# board_with_sense.net
KiCad netlist of a schematic drawn in EAGLE
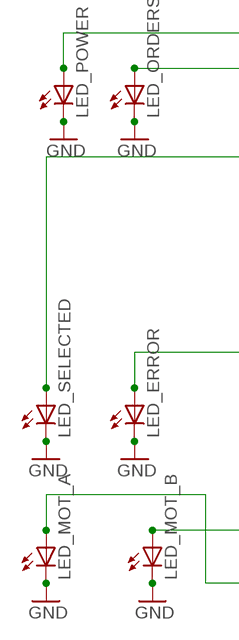
[diagram p0: schematic, sheet 1, part 1 of 2]
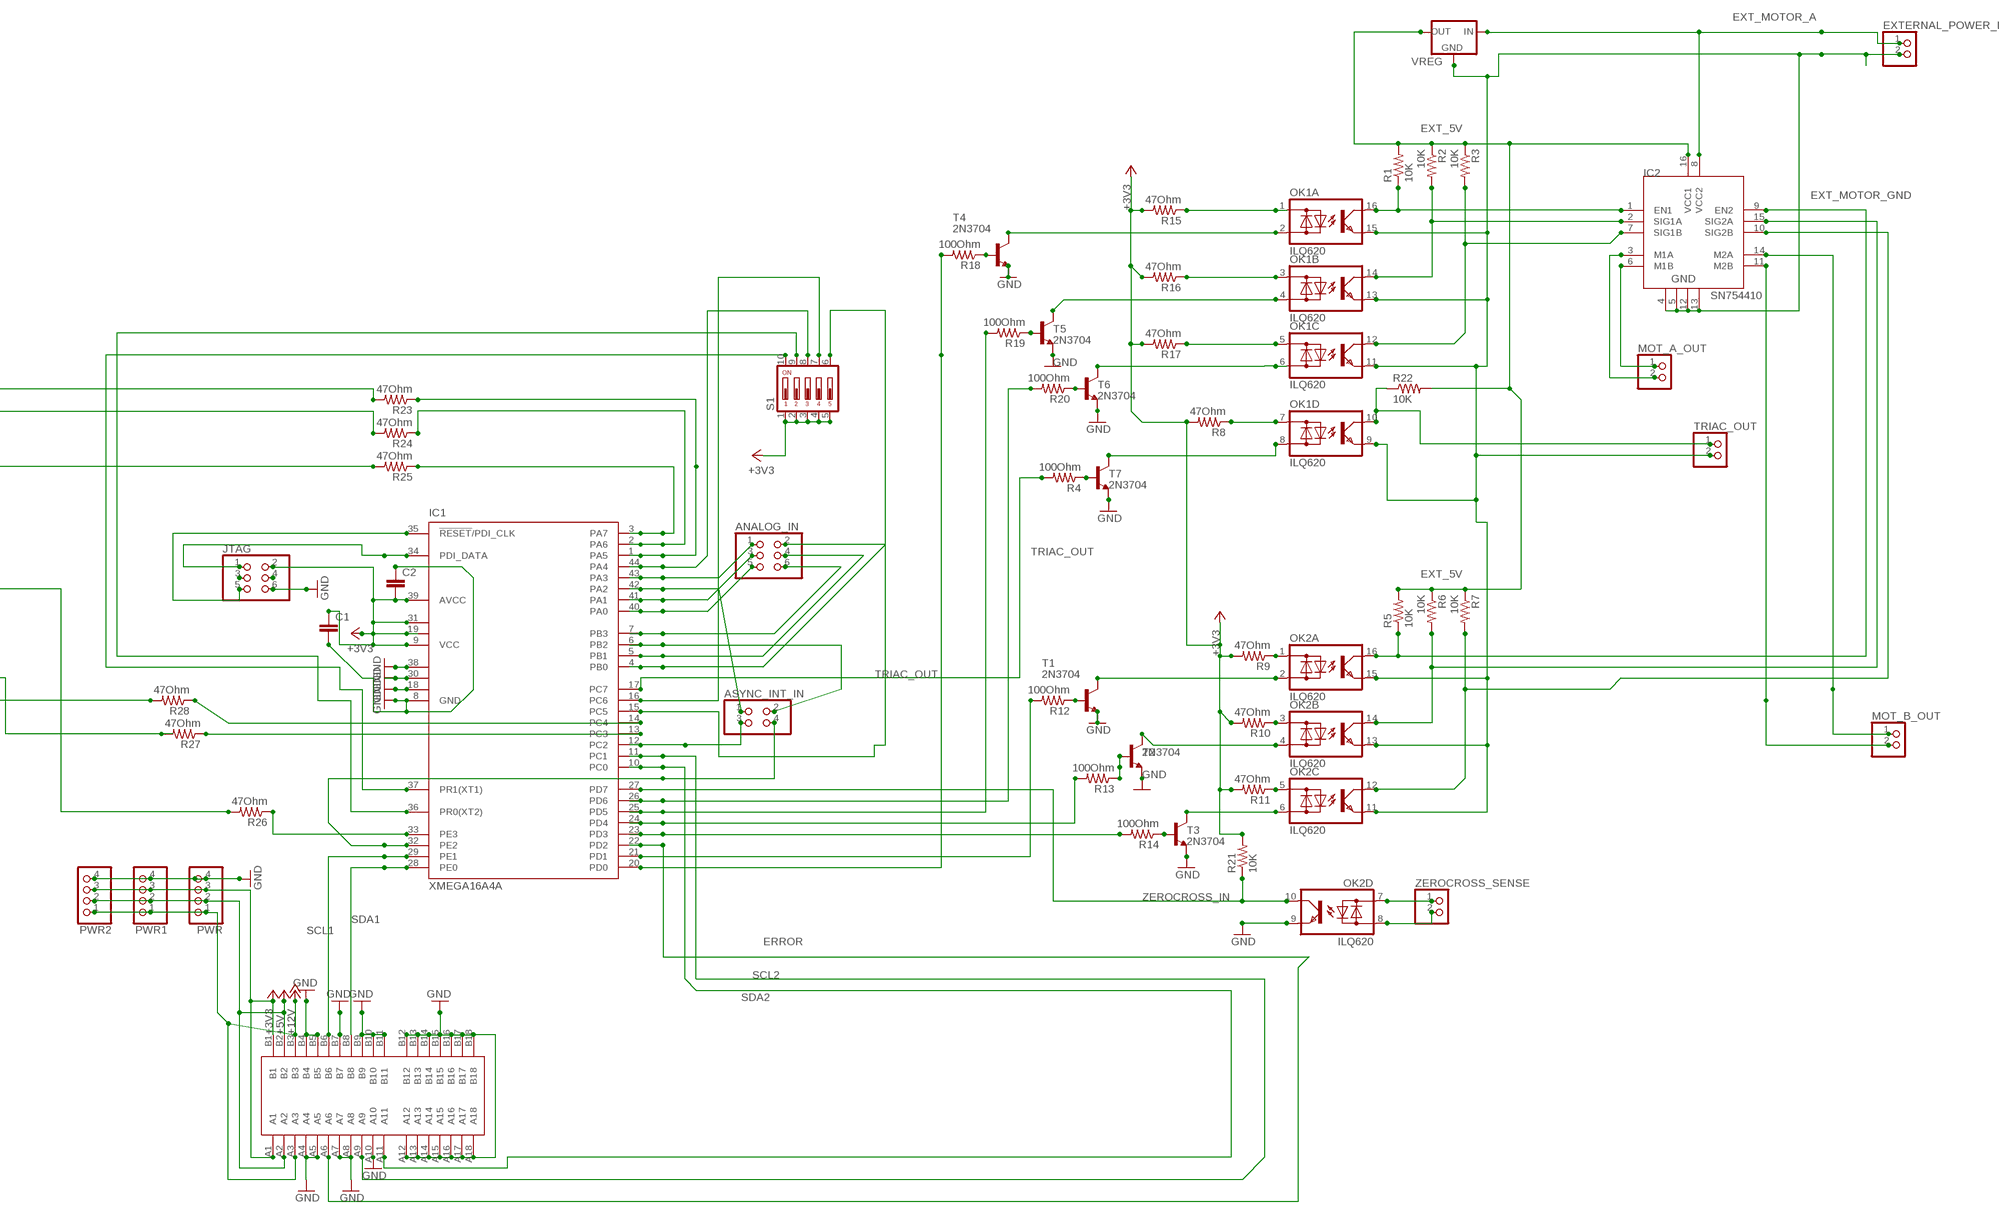
[diagram p1: schematic, sheet 1, part 2 of 2]

(export (version "E")
  (design (tool "Eeschema 10.0.6"))
  (components
    (comp (ref "ANALOG_IN")
      (value "PINHD-2X3")
      (footprint "eagle-import:2X03")
      (libsource (lib "eagle-import") (part "PINHD-2X3"))
    )
    (comp (ref "ASYNC_INT_IN")
      (value "PINHD-2X2")
      (footprint "eagle-import:2X02")
      (libsource (lib "eagle-import") (part "PINHD-2X2"))
    )
    (comp (ref "C1")
      (value "C2.5/4")
      (footprint "eagle-import:C2.5-4")
      (libsource (lib "eagle-import") (part "C2.5/4"))
    )
    (comp (ref "C2")
      (value "C2.5/4")
      (footprint "eagle-import:C2.5-4")
      (libsource (lib "eagle-import") (part "C2.5/4"))
    )
    (comp (ref "EXTERNAL_POWER_IN")
      (value "PINHD-1X2")
      (footprint "eagle-import:1X02")
      (libsource (lib "eagle-import") (part "PINHD-1X2"))
    )
    (comp (ref "IC1")
      (value "XMEGA16A4A")
      (footprint "eagle-import:TQFP44")
      (libsource (lib "eagle-import") (part "XMEGA16A4A"))
    )
    (comp (ref "IC2")
      (value "SN754410")
      (footprint "eagle-import:DIP16")
      (libsource (lib "eagle-import") (part "SN754410"))
    )
    (comp (ref "JTAG")
      (value "PINHD-2X3")
      (footprint "eagle-import:2X03")
      (libsource (lib "eagle-import") (part "PINHD-2X3"))
    )
    (comp (ref "LED_ERROR")
      (value "LED5MM")
      (footprint "eagle-import:LED5MM")
      (libsource (lib "eagle-import") (part "LED5MM"))
    )
    (comp (ref "LED_MOT_A")
      (value "LED5MM")
      (footprint "eagle-import:LED5MM")
      (libsource (lib "eagle-import") (part "LED5MM"))
    )
    (comp (ref "LED_MOT_B")
      (value "LED5MM")
      (footprint "eagle-import:LED5MM")
      (libsource (lib "eagle-import") (part "LED5MM"))
    )
    (comp (ref "LED_ORDERS")
      (value "LED5MM")
      (footprint "eagle-import:LED5MM")
      (libsource (lib "eagle-import") (part "LED5MM"))
    )
    (comp (ref "LED_POWER")
      (value "LED5MM")
      (footprint "eagle-import:LED5MM")
      (libsource (lib "eagle-import") (part "LED5MM"))
    )
    (comp (ref "LED_SELECTED")
      (value "LED5MM")
      (footprint "eagle-import:LED5MM")
      (libsource (lib "eagle-import") (part "LED5MM"))
    )
    (comp (ref "MOT_A_OUT")
      (value "PINHD-1X2")
      (footprint "eagle-import:1X02")
      (libsource (lib "eagle-import") (part "PINHD-1X2"))
    )
    (comp (ref "MOT_B_OUT")
      (value "PINHD-1X2")
      (footprint "eagle-import:1X02")
      (libsource (lib "eagle-import") (part "PINHD-1X2"))
    )
    (comp (ref "OK1")
      (value "ILQ620")
      (footprint "eagle-import:DIL16")
      (libsource (lib "eagle-import") (part "ILQ620"))
    )
    (comp (ref "OK2")
      (value "ILQ620")
      (footprint "eagle-import:DIL16")
      (libsource (lib "eagle-import") (part "ILQ620"))
    )
    (comp (ref "PWR")
      (value "PINHD-1X4")
      (footprint "eagle-import:1X04")
      (libsource (lib "eagle-import") (part "PINHD-1X4"))
    )
    (comp (ref "PWR1")
      (value "PINHD-1X4")
      (footprint "eagle-import:1X04")
      (libsource (lib "eagle-import") (part "PINHD-1X4"))
    )
    (comp (ref "PWR2")
      (value "PINHD-1X4")
      (footprint "eagle-import:1X04")
      (libsource (lib "eagle-import") (part "PINHD-1X4"))
    )
    (comp (ref "R1")
      (value "10K")
      (footprint "eagle-import:R0805")
      (libsource (lib "eagle-import") (part "R-US_R0805"))
    )
    (comp (ref "R2")
      (value "10K")
      (footprint "eagle-import:R0805")
      (libsource (lib "eagle-import") (part "R-US_R0805"))
    )
    (comp (ref "R3")
      (value "10K")
      (footprint "eagle-import:R0805")
      (libsource (lib "eagle-import") (part "R-US_R0805"))
    )
    (comp (ref "R4")
      (value "100Ohm")
      (footprint "eagle-import:0207_10")
      (libsource (lib "eagle-import") (part "R-US_0207/10"))
    )
    (comp (ref "R5")
      (value "10K")
      (footprint "eagle-import:R0805")
      (libsource (lib "eagle-import") (part "R-US_R0805"))
    )
    (comp (ref "R6")
      (value "10K")
      (footprint "eagle-import:R0805")
      (libsource (lib "eagle-import") (part "R-US_R0805"))
    )
    (comp (ref "R7")
      (value "10K")
      (footprint "eagle-import:R0805")
      (libsource (lib "eagle-import") (part "R-US_R0805"))
    )
    (comp (ref "R8")
      (value "47Ohm")
      (footprint "eagle-import:0207_10")
      (libsource (lib "eagle-import") (part "R-US_0207/10"))
    )
    (comp (ref "R9")
      (value "47Ohm")
      (footprint "eagle-import:0207_10")
      (libsource (lib "eagle-import") (part "R-US_0207/10"))
    )
    (comp (ref "R10")
      (value "47Ohm")
      (footprint "eagle-import:0207_10")
      (libsource (lib "eagle-import") (part "R-US_0207/10"))
    )
    (comp (ref "R11")
      (value "47Ohm")
      (footprint "eagle-import:0207_10")
      (libsource (lib "eagle-import") (part "R-US_0207/10"))
    )
    (comp (ref "R12")
      (value "100Ohm")
      (footprint "eagle-import:0207_10")
      (libsource (lib "eagle-import") (part "R-US_0207/10"))
    )
    (comp (ref "R13")
      (value "100Ohm")
      (footprint "eagle-import:R0805")
      (libsource (lib "eagle-import") (part "R-US_R0805"))
    )
    (comp (ref "R14")
      (value "100Ohm")
      (footprint "eagle-import:R0805")
      (libsource (lib "eagle-import") (part "R-US_R0805"))
    )
    (comp (ref "R15")
      (value "47Ohm")
      (footprint "eagle-import:0207_10")
      (libsource (lib "eagle-import") (part "R-US_0207/10"))
    )
    (comp (ref "R16")
      (value "47Ohm")
      (footprint "eagle-import:0207_10")
      (libsource (lib "eagle-import") (part "R-US_0207/10"))
    )
    (comp (ref "R17")
      (value "47Ohm")
      (footprint "eagle-import:0207_10")
      (libsource (lib "eagle-import") (part "R-US_0207/10"))
    )
    (comp (ref "R18")
      (value "100Ohm")
      (footprint "eagle-import:R0805")
      (libsource (lib "eagle-import") (part "R-US_R0805"))
    )
    (comp (ref "R19")
      (value "100Ohm")
      (footprint "eagle-import:R0805")
      (libsource (lib "eagle-import") (part "R-US_R0805"))
    )
    (comp (ref "R20")
      (value "100Ohm")
      (footprint "eagle-import:R0805")
      (libsource (lib "eagle-import") (part "R-US_R0805"))
    )
    (comp (ref "R21")
      (value "10K")
      (footprint "eagle-import:0207_10")
      (libsource (lib "eagle-import") (part "R-US_0207/10"))
    )
    (comp (ref "R22")
      (value "10K")
      (footprint "eagle-import:R0805")
      (libsource (lib "eagle-import") (part "R-US_R0805"))
    )
    (comp (ref "R23")
      (value "47Ohm")
      (footprint "eagle-import:0204_7")
      (libsource (lib "eagle-import") (part "R-US_0204/7"))
    )
    (comp (ref "R24")
      (value "47Ohm")
      (footprint "eagle-import:0204_7")
      (libsource (lib "eagle-import") (part "R-US_0204/7"))
    )
    (comp (ref "R25")
      (value "47Ohm")
      (footprint "eagle-import:0204_7")
      (libsource (lib "eagle-import") (part "R-US_0204/7"))
    )
    (comp (ref "R26")
      (value "47Ohm")
      (footprint "eagle-import:0204_7")
      (libsource (lib "eagle-import") (part "R-US_0204/7"))
    )
    (comp (ref "R27")
      (value "47Ohm")
      (footprint "eagle-import:0204_7")
      (libsource (lib "eagle-import") (part "R-US_0204/7"))
    )
    (comp (ref "R28")
      (value "47Ohm")
      (footprint "eagle-import:0204_7")
      (libsource (lib "eagle-import") (part "R-US_0204/7"))
    )
    (comp (ref "S1")
      (value "DA05")
      (footprint "eagle-import:DA-05")
      (libsource (lib "eagle-import") (part "DA05"))
    )
    (comp (ref "T1")
      (value "2N3704")
      (footprint "eagle-import:TO92")
      (libsource (lib "eagle-import") (part "2N3704"))
    )
    (comp (ref "T2")
      (value "2N3704")
      (footprint "eagle-import:TO92")
      (libsource (lib "eagle-import") (part "2N3704"))
    )
    (comp (ref "T3")
      (value "2N3704")
      (footprint "eagle-import:TO92")
      (libsource (lib "eagle-import") (part "2N3704"))
    )
    (comp (ref "T4")
      (value "2N3704")
      (footprint "eagle-import:TO92")
      (libsource (lib "eagle-import") (part "2N3704"))
    )
    (comp (ref "T5")
      (value "2N3704")
      (footprint "eagle-import:TO92")
      (libsource (lib "eagle-import") (part "2N3704"))
    )
    (comp (ref "T6")
      (value "2N3704")
      (footprint "eagle-import:TO92")
      (libsource (lib "eagle-import") (part "2N3704"))
    )
    (comp (ref "T7")
      (value "2N3704")
      (footprint "eagle-import:TO92")
      (libsource (lib "eagle-import") (part "2N3704"))
    )
    (comp (ref "TRIAC_OUT")
      (value "PINHD-1X2")
      (footprint "eagle-import:1X02")
      (libsource (lib "eagle-import") (part "PINHD-1X2"))
    )
    (comp (ref "VREG")
      (value "78MXXL")
      (footprint "eagle-import:78MXXL")
      (libsource (lib "eagle-import") (part "78MXXL"))
    )
    (comp (ref "X1")
      (value "PCI-E1X_EDGE")
      (footprint "eagle-import:PCI-E_X1_EDGE")
      (libsource (lib "eagle-import") (part "PCI-E1X_EDGE"))
    )
    (comp (ref "ZEROCROSS_SENSE")
      (value "PINHD-1X2")
      (footprint "eagle-import:1X02")
      (libsource (lib "eagle-import") (part "PINHD-1X2"))
    )
  )
  (nets
    (net (code "1") (name "+3V3") (class "Default")
      (node (ref "C1") (pin "1") (pinfunction "1_1") (pintype "passive"))
      (node (ref "C2") (pin "2") (pinfunction "2_2") (pintype "passive"))
      (node (ref "IC1") (pin "19") (pinfunction "VCC1_19") (pintype "power_in"))
      (node (ref "IC1") (pin "31") (pinfunction "VCC2_31") (pintype "power_in"))
      (node (ref "IC1") (pin "39") (pinfunction "AVCC_39") (pintype "power_in"))
      (node (ref "IC1") (pin "9") (pinfunction "VCC_9") (pintype "power_in"))
      (node (ref "JTAG") (pin "2") (pinfunction "2_2") (pintype "passive"))
      (node (ref "PWR") (pin "3") (pinfunction "3_3") (pintype "passive"))
      (node (ref "PWR1") (pin "3") (pinfunction "3_3") (pintype "passive"))
      (node (ref "PWR2") (pin "3") (pinfunction "3_3") (pintype "passive"))
      (node (ref "R10") (pin "2") (pinfunction "2_2") (pintype "passive"))
      (node (ref "R11") (pin "2") (pinfunction "2_2") (pintype "passive"))
      (node (ref "R15") (pin "2") (pinfunction "2_2") (pintype "passive"))
      (node (ref "R16") (pin "2") (pinfunction "2_2") (pintype "passive"))
      (node (ref "R17") (pin "2") (pinfunction "2_2") (pintype "passive"))
      (node (ref "R21") (pin "2") (pinfunction "2_2") (pintype "passive"))
      (node (ref "R8") (pin "2") (pinfunction "2_2") (pintype "passive"))
      (node (ref "R9") (pin "2") (pinfunction "2_2") (pintype "passive"))
      (node (ref "S1") (pin "1") (pinfunction "1_1") (pintype "passive"))
      (node (ref "S1") (pin "2") (pinfunction "2_2") (pintype "passive"))
      (node (ref "S1") (pin "3") (pinfunction "3_3") (pintype "passive"))
      (node (ref "S1") (pin "4") (pinfunction "4_4") (pintype "passive"))
      (node (ref "S1") (pin "5") (pinfunction "5_5") (pintype "passive"))
      (node (ref "X1") (pin "A1") (pinfunction "A1_A1") (pintype "bidirectional"))
      (node (ref "X1") (pin "B1") (pinfunction "B1_B1") (pintype "bidirectional"))
    )
    (net (code "2") (name "+5V") (class "Default")
      (node (ref "PWR") (pin "2") (pinfunction "2_2") (pintype "passive"))
      (node (ref "PWR1") (pin "2") (pinfunction "2_2") (pintype "passive"))
      (node (ref "PWR2") (pin "2") (pinfunction "2_2") (pintype "passive"))
      (node (ref "X1") (pin "A2") (pinfunction "A2_A2") (pintype "bidirectional"))
      (node (ref "X1") (pin "B2") (pinfunction "B2_B2") (pintype "bidirectional"))
    )
    (net (code "3") (name "+12V") (class "Default")
      (node (ref "PWR") (pin "1") (pinfunction "1_1") (pintype "passive"))
      (node (ref "PWR1") (pin "1") (pinfunction "1_1") (pintype "passive"))
      (node (ref "PWR2") (pin "1") (pinfunction "1_1") (pintype "passive"))
      (node (ref "X1") (pin "A3") (pinfunction "A3_A3") (pintype "bidirectional"))
      (node (ref "X1") (pin "B3") (pinfunction "B3_B3") (pintype "bidirectional"))
    )
    (net (code "4") (name "ERROR") (class "Default")
      (node (ref "IC1") (pin "22") (pinfunction "PD2_22") (pintype "bidirectional"))
      (node (ref "X1") (pin "A6") (pinfunction "A6_A6") (pintype "bidirectional"))
    )
    (net (code "5") (name "EXT_5V") (class "Default")
      (node (ref "IC2") (pin "16") (pinfunction "VCC1_16") (pintype "power_in"))
      (node (ref "R1") (pin "2") (pinfunction "2_2") (pintype "passive"))
      (node (ref "R2") (pin "1") (pinfunction "1_1") (pintype "passive"))
      (node (ref "R22") (pin "2") (pinfunction "2_2") (pintype "passive"))
      (node (ref "R3") (pin "1") (pinfunction "1_1") (pintype "passive"))
      (node (ref "R5") (pin "2") (pinfunction "2_2") (pintype "passive"))
      (node (ref "R6") (pin "1") (pinfunction "1_1") (pintype "passive"))
      (node (ref "R7") (pin "1") (pinfunction "1_1") (pintype "passive"))
      (node (ref "VREG") (pin "OUT") (pinfunction "OUT_OUT") (pintype "passive"))
    )
    (net (code "6") (name "EXT_MOTOR_A") (class "Default")
      (node (ref "EXTERNAL_POWER_IN") (pin "1") (pinfunction "1_1") (pintype "passive"))
      (node (ref "IC2") (pin "8") (pinfunction "VCC2_8") (pintype "power_in"))
      (node (ref "VREG") (pin "IN") (pinfunction "IN_IN") (pintype "input"))
    )
    (net (code "7") (name "EXT_MOTOR_GND") (class "Default")
      (node (ref "EXTERNAL_POWER_IN") (pin "2") (pinfunction "2_2") (pintype "passive"))
      (node (ref "IC2") (pin "12") (pinfunction "P12_12") (pintype "power_in"))
      (node (ref "IC2") (pin "13") (pinfunction "P13_13") (pintype "power_in"))
      (node (ref "IC2") (pin "4") (pinfunction "P4_4") (pintype "power_in"))
      (node (ref "IC2") (pin "5") (pinfunction "P5_5") (pintype "power_in"))
      (node (ref "OK1") (pin "11") (pinfunction "E_11") (pintype "passive"))
      (node (ref "OK1") (pin "13") (pinfunction "E_13") (pintype "passive"))
      (node (ref "OK1") (pin "15") (pinfunction "E_15") (pintype "passive"))
      (node (ref "OK1") (pin "9") (pinfunction "E_9") (pintype "passive"))
      (node (ref "OK2") (pin "11") (pinfunction "E_11") (pintype "passive"))
      (node (ref "OK2") (pin "13") (pinfunction "E_13") (pintype "passive"))
      (node (ref "OK2") (pin "15") (pinfunction "E_15") (pintype "passive"))
      (node (ref "TRIAC_OUT") (pin "2") (pinfunction "2_2") (pintype "passive"))
      (node (ref "VREG") (pin "GND") (pinfunction "GND_GND") (pintype "input"))
    )
    (net (code "8") (name "GND") (class "Default")
      (node (ref "C1") (pin "2") (pinfunction "2_2") (pintype "passive"))
      (node (ref "C2") (pin "1") (pinfunction "1_1") (pintype "passive"))
      (node (ref "IC1") (pin "18") (pinfunction "GND1_18") (pintype "power_in"))
      (node (ref "IC1") (pin "30") (pinfunction "GND2_30") (pintype "power_in"))
      (node (ref "IC1") (pin "38") (pinfunction "GND3_38") (pintype "power_in"))
      (node (ref "IC1") (pin "8") (pinfunction "GND_8") (pintype "power_in"))
      (node (ref "JTAG") (pin "6") (pinfunction "6_6") (pintype "passive"))
      (node (ref "LED_ERROR") (pin "K") (pinfunction "C_K") (pintype "passive"))
      (node (ref "LED_MOT_A") (pin "K") (pinfunction "C_K") (pintype "passive"))
      (node (ref "LED_MOT_B") (pin "K") (pinfunction "C_K") (pintype "passive"))
      (node (ref "LED_ORDERS") (pin "K") (pinfunction "C_K") (pintype "passive"))
      (node (ref "LED_POWER") (pin "K") (pinfunction "C_K") (pintype "passive"))
      (node (ref "LED_SELECTED") (pin "K") (pinfunction "C_K") (pintype "passive"))
      (node (ref "OK2") (pin "9") (pinfunction "E_9") (pintype "passive"))
      (node (ref "PWR") (pin "4") (pinfunction "4_4") (pintype "passive"))
      (node (ref "PWR1") (pin "4") (pinfunction "4_4") (pintype "passive"))
      (node (ref "PWR2") (pin "4") (pinfunction "4_4") (pintype "passive"))
      (node (ref "T1") (pin "3") (pinfunction "E_3") (pintype "passive"))
      (node (ref "T2") (pin "3") (pinfunction "E_3") (pintype "passive"))
      (node (ref "T3") (pin "3") (pinfunction "E_3") (pintype "passive"))
      (node (ref "T4") (pin "3") (pinfunction "E_3") (pintype "passive"))
      (node (ref "T5") (pin "3") (pinfunction "E_3") (pintype "passive"))
      (node (ref "T6") (pin "3") (pinfunction "E_3") (pintype "passive"))
      (node (ref "T7") (pin "3") (pinfunction "E_3") (pintype "passive"))
      (node (ref "X1") (pin "A10") (pinfunction "A10_A10") (pintype "bidirectional"))
      (node (ref "X1") (pin "A12") (pinfunction "A12_A12") (pintype "bidirectional"))
      (node (ref "X1") (pin "A13") (pinfunction "A13_A13") (pintype "bidirectional"))
      (node (ref "X1") (pin "A14") (pinfunction "A14_A14") (pintype "bidirectional"))
      (node (ref "X1") (pin "A15") (pinfunction "A15_A15") (pintype "bidirectional"))
      (node (ref "X1") (pin "A16") (pinfunction "A16_A16") (pintype "bidirectional"))
      (node (ref "X1") (pin "A17") (pinfunction "A17_A17") (pintype "bidirectional"))
      (node (ref "X1") (pin "A18") (pinfunction "A18_A18") (pintype "bidirectional"))
      (node (ref "X1") (pin "A4") (pinfunction "A4_A4") (pintype "bidirectional"))
      (node (ref "X1") (pin "A5") (pinfunction "A5_A5") (pintype "bidirectional"))
      (node (ref "X1") (pin "A7") (pinfunction "A7_A7") (pintype "bidirectional"))
      (node (ref "X1") (pin "A8") (pinfunction "A8_A8") (pintype "bidirectional"))
      (node (ref "X1") (pin "B10") (pinfunction "B10_B10") (pintype "bidirectional"))
      (node (ref "X1") (pin "B11") (pinfunction "B11_B11") (pintype "bidirectional"))
      (node (ref "X1") (pin "B12") (pinfunction "B12_B12") (pintype "bidirectional"))
      (node (ref "X1") (pin "B13") (pinfunction "B13_B13") (pintype "bidirectional"))
      (node (ref "X1") (pin "B14") (pinfunction "B14_B14") (pintype "bidirectional"))
      (node (ref "X1") (pin "B15") (pinfunction "B15_B15") (pintype "bidirectional"))
      (node (ref "X1") (pin "B16") (pinfunction "B16_B16") (pintype "bidirectional"))
      (node (ref "X1") (pin "B17") (pinfunction "B17_B17") (pintype "bidirectional"))
      (node (ref "X1") (pin "B18") (pinfunction "B18_B18") (pintype "bidirectional"))
      (node (ref "X1") (pin "B4") (pinfunction "B4_B4") (pintype "bidirectional"))
      (node (ref "X1") (pin "B5") (pinfunction "B5_B5") (pintype "bidirectional"))
      (node (ref "X1") (pin "B7") (pinfunction "B7_B7") (pintype "bidirectional"))
      (node (ref "X1") (pin "B9") (pinfunction "B9_B9") (pintype "bidirectional"))
    )
    (net (code "9") (name "Net-(IC1-PA0)") (class "Default")
      (node (ref "ANALOG_IN") (pin "5") (pinfunction "5_5") (pintype "passive"))
      (node (ref "IC1") (pin "40") (pinfunction "PA0_40") (pintype "bidirectional"))
    )
    (net (code "10") (name "Net-(IC1-PA1)") (class "Default")
      (node (ref "ANALOG_IN") (pin "3") (pinfunction "3_3") (pintype "passive"))
      (node (ref "IC1") (pin "41") (pinfunction "PA1_41") (pintype "bidirectional"))
    )
    (net (code "11") (name "Net-(IC1-PA2)") (class "Default")
      (node (ref "ASYNC_INT_IN") (pin "1") (pinfunction "1_1") (pintype "passive"))
      (node (ref "IC1") (pin "42") (pinfunction "PA2_42") (pintype "bidirectional"))
    )
    (net (code "12") (name "Net-(IC1-PA3)") (class "Default")
      (node (ref "ANALOG_IN") (pin "1") (pinfunction "1_1") (pintype "passive"))
      (node (ref "IC1") (pin "43") (pinfunction "PA3_43") (pintype "bidirectional"))
    )
    (net (code "13") (name "Net-(IC1-PA4)") (class "Default")
      (node (ref "IC1") (pin "44") (pinfunction "PA4_44") (pintype "bidirectional"))
      (node (ref "S1") (pin "8") (pinfunction "8_8") (pintype "passive"))
    )
    (net (code "14") (name "Net-(IC1-PA5)") (class "Default")
      (node (ref "IC1") (pin "1") (pinfunction "PA5_1") (pintype "bidirectional"))
      (node (ref "R23") (pin "1") (pinfunction "1_1") (pintype "passive"))
    )
    (net (code "15") (name "Net-(IC1-PA6)") (class "Default")
      (node (ref "IC1") (pin "2") (pinfunction "PA6_2") (pintype "bidirectional"))
      (node (ref "R24") (pin "1") (pinfunction "1_1") (pintype "passive"))
    )
    (net (code "16") (name "Net-(IC1-PA7)") (class "Default")
      (node (ref "IC1") (pin "3") (pinfunction "PA7_3") (pintype "bidirectional"))
      (node (ref "R25") (pin "1") (pinfunction "1_1") (pintype "passive"))
    )
    (net (code "17") (name "Net-(IC1-PB0)") (class "Default")
      (node (ref "ANALOG_IN") (pin "2") (pinfunction "2_2") (pintype "passive"))
      (node (ref "IC1") (pin "4") (pinfunction "PB0_4") (pintype "bidirectional"))
    )
    (net (code "18") (name "Net-(IC1-PB1)") (class "Default")
      (node (ref "ANALOG_IN") (pin "4") (pinfunction "4_4") (pintype "passive"))
      (node (ref "IC1") (pin "5") (pinfunction "PB1_5") (pintype "bidirectional"))
    )
    (net (code "19") (name "Net-(IC1-PB2)") (class "Default")
      (node (ref "ASYNC_INT_IN") (pin "2") (pinfunction "2_2") (pintype "passive"))
      (node (ref "IC1") (pin "6") (pinfunction "PB2_6") (pintype "bidirectional"))
    )
    (net (code "20") (name "Net-(IC1-PB3)") (class "Default")
      (node (ref "ANALOG_IN") (pin "6") (pinfunction "6_6") (pintype "passive"))
      (node (ref "IC1") (pin "7") (pinfunction "PB3_7") (pintype "bidirectional"))
    )
    (net (code "21") (name "Net-(IC1-PC2)") (class "Default")
      (node (ref "ASYNC_INT_IN") (pin "3") (pinfunction "3_3") (pintype "passive"))
      (node (ref "IC1") (pin "12") (pinfunction "PC2_12") (pintype "bidirectional"))
    )
    (net (code "22") (name "Net-(IC1-PC3)") (class "Default")
      (node (ref "IC1") (pin "13") (pinfunction "PC3_13") (pintype "bidirectional"))
      (node (ref "R27") (pin "1") (pinfunction "1_1") (pintype "passive"))
    )
    (net (code "23") (name "Net-(IC1-PC4)") (class "Default")
      (node (ref "IC1") (pin "14") (pinfunction "PC4_14") (pintype "bidirectional"))
      (node (ref "R28") (pin "1") (pinfunction "1_1") (pintype "passive"))
    )
    (net (code "24") (name "Net-(IC1-PC5)") (class "Default")
      (node (ref "IC1") (pin "15") (pinfunction "PC5_15") (pintype "bidirectional"))
      (node (ref "S1") (pin "6") (pinfunction "6_6") (pintype "passive"))
    )
    (net (code "25") (name "Net-(IC1-PC6)") (class "Default")
      (node (ref "IC1") (pin "16") (pinfunction "PC6_16") (pintype "bidirectional"))
      (node (ref "S1") (pin "7") (pinfunction "7_7") (pintype "passive"))
    )
    (net (code "26") (name "Net-(IC1-PD0)") (class "Default")
      (node (ref "IC1") (pin "20") (pinfunction "PD0_20") (pintype "bidirectional"))
      (node (ref "R18") (pin "2") (pinfunction "2_2") (pintype "passive"))
    )
    (net (code "27") (name "Net-(IC1-PD1)") (class "Default")
      (node (ref "IC1") (pin "21") (pinfunction "PD1_21") (pintype "bidirectional"))
      (node (ref "R12") (pin "2") (pinfunction "2_2") (pintype "passive"))
    )
    (net (code "28") (name "Net-(IC1-PD3)") (class "Default")
      (node (ref "IC1") (pin "23") (pinfunction "PD3_23") (pintype "bidirectional"))
      (node (ref "R14") (pin "2") (pinfunction "2_2") (pintype "passive"))
    )
    (net (code "29") (name "Net-(IC1-PD4)") (class "Default")
      (node (ref "IC1") (pin "24") (pinfunction "PD4_24") (pintype "bidirectional"))
      (node (ref "R13") (pin "2") (pinfunction "2_2") (pintype "passive"))
    )
    (net (code "30") (name "Net-(IC1-PD5)") (class "Default")
      (node (ref "IC1") (pin "25") (pinfunction "PD5_25") (pintype "bidirectional"))
      (node (ref "R19") (pin "2") (pinfunction "2_2") (pintype "passive"))
    )
    (net (code "31") (name "Net-(IC1-PD6)") (class "Default")
      (node (ref "IC1") (pin "26") (pinfunction "PD6_26") (pintype "bidirectional"))
      (node (ref "R20") (pin "2") (pinfunction "2_2") (pintype "passive"))
    )
    (net (code "32") (name "Net-(IC1-PDI_DATA)") (class "Default")
      (node (ref "IC1") (pin "34") (pinfunction "PDI_DATA_34") (pintype "bidirectional"))
      (node (ref "JTAG") (pin "1") (pinfunction "1_1") (pintype "passive"))
    )
    (net (code "33") (name "Net-(IC1-PE2)") (class "Default")
      (node (ref "ASYNC_INT_IN") (pin "4") (pinfunction "4_4") (pintype "passive"))
      (node (ref "IC1") (pin "32") (pinfunction "PE2_32") (pintype "bidirectional"))
    )
    (net (code "34") (name "Net-(IC1-PE3)") (class "Default")
      (node (ref "IC1") (pin "33") (pinfunction "PE3_33") (pintype "bidirectional"))
      (node (ref "R26") (pin "1") (pinfunction "1_1") (pintype "passive"))
    )
    (net (code "35") (name "Net-(IC1-PR0(XT2))") (class "Default")
      (node (ref "IC1") (pin "36") (pinfunction "PR0(XT2)_36") (pintype "bidirectional"))
      (node (ref "S1") (pin "9") (pinfunction "9_9") (pintype "passive"))
    )
    (net (code "36") (name "Net-(IC1-PR1(XT1))") (class "Default")
      (node (ref "IC1") (pin "37") (pinfunction "PR1(XT1)_37") (pintype "bidirectional"))
      (node (ref "S1") (pin "10") (pinfunction "10_10") (pintype "passive"))
    )
    (net (code "37") (name "Net-(IC1-~{RESET}{slash}PDI_CLK)") (class "Default")
      (node (ref "IC1") (pin "35") (pinfunction "~{RESET}/PDI_CLK_35") (pintype "bidirectional"))
      (node (ref "JTAG") (pin "5") (pinfunction "5_5") (pintype "passive"))
    )
    (net (code "38") (name "Net-(IC2-EN1)") (class "Default")
      (node (ref "IC2") (pin "1") (pinfunction "EN1_1") (pintype "bidirectional"))
      (node (ref "OK1") (pin "16") (pinfunction "C_16") (pintype "passive"))
      (node (ref "R1") (pin "1") (pinfunction "1_1") (pintype "passive"))
    )
    (net (code "39") (name "Net-(IC2-EN2)") (class "Default")
      (node (ref "IC2") (pin "9") (pinfunction "EN2_9") (pintype "bidirectional"))
      (node (ref "OK2") (pin "16") (pinfunction "C_16") (pintype "passive"))
      (node (ref "R5") (pin "1") (pinfunction "1_1") (pintype "passive"))
    )
    (net (code "40") (name "Net-(IC2-M1A)") (class "Default")
      (node (ref "IC2") (pin "3") (pinfunction "M1A_3") (pintype "bidirectional"))
      (node (ref "MOT_A_OUT") (pin "2") (pinfunction "2_2") (pintype "passive"))
    )
    (net (code "41") (name "Net-(IC2-M1B)") (class "Default")
      (node (ref "IC2") (pin "6") (pinfunction "M1B_6") (pintype "bidirectional"))
      (node (ref "MOT_A_OUT") (pin "1") (pinfunction "1_1") (pintype "passive"))
    )
    (net (code "42") (name "Net-(IC2-M2A)") (class "Default")
      (node (ref "IC2") (pin "14") (pinfunction "M2A_14") (pintype "bidirectional"))
      (node (ref "MOT_B_OUT") (pin "1") (pinfunction "1_1") (pintype "passive"))
    )
    (net (code "43") (name "Net-(IC2-M2B)") (class "Default")
      (node (ref "IC2") (pin "11") (pinfunction "M2B_11") (pintype "bidirectional"))
      (node (ref "MOT_B_OUT") (pin "2") (pinfunction "2_2") (pintype "passive"))
    )
    (net (code "44") (name "Net-(IC2-SIG1A)") (class "Default")
      (node (ref "IC2") (pin "2") (pinfunction "SIG1A_2") (pintype "bidirectional"))
      (node (ref "OK1") (pin "14") (pinfunction "C_14") (pintype "passive"))
      (node (ref "R2") (pin "2") (pinfunction "2_2") (pintype "passive"))
    )
    (net (code "45") (name "Net-(IC2-SIG1B)") (class "Default")
      (node (ref "IC2") (pin "7") (pinfunction "SIG1B_7") (pintype "bidirectional"))
      (node (ref "OK1") (pin "12") (pinfunction "C_12") (pintype "passive"))
      (node (ref "R3") (pin "2") (pinfunction "2_2") (pintype "passive"))
    )
    (net (code "46") (name "Net-(IC2-SIG2A)") (class "Default")
      (node (ref "IC2") (pin "15") (pinfunction "SIG2A_15") (pintype "bidirectional"))
      (node (ref "OK2") (pin "14") (pinfunction "C_14") (pintype "passive"))
      (node (ref "R6") (pin "2") (pinfunction "2_2") (pintype "passive"))
    )
    (net (code "47") (name "Net-(IC2-SIG2B)") (class "Default")
      (node (ref "IC2") (pin "10") (pinfunction "SIG2B_10") (pintype "bidirectional"))
      (node (ref "OK2") (pin "12") (pinfunction "C_12") (pintype "passive"))
      (node (ref "R7") (pin "2") (pinfunction "2_2") (pintype "passive"))
    )
    (net (code "48") (name "Net-(LED_ERROR-PadA)") (class "Default")
      (node (ref "LED_ERROR") (pin "A") (pinfunction "A_A") (pintype "passive"))
      (node (ref "R26") (pin "2") (pinfunction "2_2") (pintype "passive"))
    )
    (net (code "49") (name "Net-(LED_MOT_A-PadA)") (class "Default")
      (node (ref "LED_MOT_A") (pin "A") (pinfunction "A_A") (pintype "passive"))
      (node (ref "R27") (pin "2") (pinfunction "2_2") (pintype "passive"))
    )
    (net (code "50") (name "Net-(LED_MOT_B-PadA)") (class "Default")
      (node (ref "LED_MOT_B") (pin "A") (pinfunction "A_A") (pintype "passive"))
      (node (ref "R28") (pin "2") (pinfunction "2_2") (pintype "passive"))
    )
    (net (code "51") (name "Net-(LED_ORDERS-PadA)") (class "Default")
      (node (ref "LED_ORDERS") (pin "A") (pinfunction "A_A") (pintype "passive"))
      (node (ref "R24") (pin "2") (pinfunction "2_2") (pintype "passive"))
    )
    (net (code "52") (name "Net-(LED_POWER-PadA)") (class "Default")
      (node (ref "LED_POWER") (pin "A") (pinfunction "A_A") (pintype "passive"))
      (node (ref "R23") (pin "2") (pinfunction "2_2") (pintype "passive"))
    )
    (net (code "53") (name "Net-(LED_SELECTED-PadA)") (class "Default")
      (node (ref "LED_SELECTED") (pin "A") (pinfunction "A_A") (pintype "passive"))
      (node (ref "R25") (pin "2") (pinfunction "2_2") (pintype "passive"))
    )
    (net (code "54") (name "Net-(OK1A-AC1)") (class "Default")
      (node (ref "OK1") (pin "1") (pinfunction "AC1_1") (pintype "passive"))
      (node (ref "R15") (pin "1") (pinfunction "1_1") (pintype "passive"))
    )
    (net (code "55") (name "Net-(OK1A-AC2)") (class "Default")
      (node (ref "OK1") (pin "2") (pinfunction "AC2_2") (pintype "passive"))
      (node (ref "T4") (pin "2") (pinfunction "C_2") (pintype "passive"))
    )
    (net (code "56") (name "Net-(OK1B-AC1)") (class "Default")
      (node (ref "OK1") (pin "3") (pinfunction "AC1_3") (pintype "passive"))
      (node (ref "R16") (pin "1") (pinfunction "1_1") (pintype "passive"))
    )
    (net (code "57") (name "Net-(OK1B-AC2)") (class "Default")
      (node (ref "OK1") (pin "4") (pinfunction "AC2_4") (pintype "passive"))
      (node (ref "T5") (pin "2") (pinfunction "C_2") (pintype "passive"))
    )
    (net (code "58") (name "Net-(OK1C-AC1)") (class "Default")
      (node (ref "OK1") (pin "5") (pinfunction "AC1_5") (pintype "passive"))
      (node (ref "R17") (pin "1") (pinfunction "1_1") (pintype "passive"))
    )
    (net (code "59") (name "Net-(OK1C-AC2)") (class "Default")
      (node (ref "OK1") (pin "6") (pinfunction "AC2_6") (pintype "passive"))
      (node (ref "T6") (pin "2") (pinfunction "C_2") (pintype "passive"))
    )
    (net (code "60") (name "Net-(OK1D-AC1)") (class "Default")
      (node (ref "OK1") (pin "7") (pinfunction "AC1_7") (pintype "passive"))
      (node (ref "R8") (pin "1") (pinfunction "1_1") (pintype "passive"))
    )
    (net (code "61") (name "Net-(OK1D-AC2)") (class "Default")
      (node (ref "OK1") (pin "8") (pinfunction "AC2_8") (pintype "passive"))
      (node (ref "T7") (pin "2") (pinfunction "C_2") (pintype "passive"))
    )
    (net (code "62") (name "Net-(OK1D-C)") (class "Default")
      (node (ref "OK1") (pin "10") (pinfunction "C_10") (pintype "passive"))
      (node (ref "R22") (pin "1") (pinfunction "1_1") (pintype "passive"))
      (node (ref "TRIAC_OUT") (pin "1") (pinfunction "1_1") (pintype "passive"))
    )
    (net (code "63") (name "Net-(OK2A-AC1)") (class "Default")
      (node (ref "OK2") (pin "1") (pinfunction "AC1_1") (pintype "passive"))
      (node (ref "R9") (pin "1") (pinfunction "1_1") (pintype "passive"))
    )
    (net (code "64") (name "Net-(OK2A-AC2)") (class "Default")
      (node (ref "OK2") (pin "2") (pinfunction "AC2_2") (pintype "passive"))
      (node (ref "T1") (pin "2") (pinfunction "C_2") (pintype "passive"))
    )
    (net (code "65") (name "Net-(OK2B-AC1)") (class "Default")
      (node (ref "OK2") (pin "3") (pinfunction "AC1_3") (pintype "passive"))
      (node (ref "R10") (pin "1") (pinfunction "1_1") (pintype "passive"))
    )
    (net (code "66") (name "Net-(OK2B-AC2)") (class "Default")
      (node (ref "OK2") (pin "4") (pinfunction "AC2_4") (pintype "passive"))
      (node (ref "T2") (pin "2") (pinfunction "C_2") (pintype "passive"))
    )
    (net (code "67") (name "Net-(OK2C-AC1)") (class "Default")
      (node (ref "OK2") (pin "5") (pinfunction "AC1_5") (pintype "passive"))
      (node (ref "R11") (pin "1") (pinfunction "1_1") (pintype "passive"))
    )
    (net (code "68") (name "Net-(OK2C-AC2)") (class "Default")
      (node (ref "OK2") (pin "6") (pinfunction "AC2_6") (pintype "passive"))
      (node (ref "T3") (pin "2") (pinfunction "C_2") (pintype "passive"))
    )
    (net (code "69") (name "Net-(OK2D-AC1)") (class "Default")
      (node (ref "OK2") (pin "7") (pinfunction "AC1_7") (pintype "passive"))
      (node (ref "ZEROCROSS_SENSE") (pin "1") (pinfunction "1_1") (pintype "passive"))
    )
    (net (code "70") (name "Net-(OK2D-AC2)") (class "Default")
      (node (ref "OK2") (pin "8") (pinfunction "AC2_8") (pintype "passive"))
      (node (ref "ZEROCROSS_SENSE") (pin "2") (pinfunction "2_2") (pintype "passive"))
    )
    (net (code "71") (name "Net-(T1-B)") (class "Default")
      (node (ref "R12") (pin "1") (pinfunction "1_1") (pintype "passive"))
      (node (ref "T1") (pin "1") (pinfunction "B_1") (pintype "passive"))
    )
    (net (code "72") (name "Net-(T2-B)") (class "Default")
      (node (ref "R13") (pin "1") (pinfunction "1_1") (pintype "passive"))
      (node (ref "T2") (pin "1") (pinfunction "B_1") (pintype "passive"))
    )
    (net (code "73") (name "Net-(T3-B)") (class "Default")
      (node (ref "R14") (pin "1") (pinfunction "1_1") (pintype "passive"))
      (node (ref "T3") (pin "1") (pinfunction "B_1") (pintype "passive"))
    )
    (net (code "74") (name "Net-(T4-B)") (class "Default")
      (node (ref "R18") (pin "1") (pinfunction "1_1") (pintype "passive"))
      (node (ref "T4") (pin "1") (pinfunction "B_1") (pintype "passive"))
    )
    (net (code "75") (name "Net-(T5-B)") (class "Default")
      (node (ref "R19") (pin "1") (pinfunction "1_1") (pintype "passive"))
      (node (ref "T5") (pin "1") (pinfunction "B_1") (pintype "passive"))
    )
    (net (code "76") (name "Net-(T6-B)") (class "Default")
      (node (ref "R20") (pin "1") (pinfunction "1_1") (pintype "passive"))
      (node (ref "T6") (pin "1") (pinfunction "B_1") (pintype "passive"))
    )
    (net (code "77") (name "Net-(T7-B)") (class "Default")
      (node (ref "R4") (pin "1") (pinfunction "1_1") (pintype "passive"))
      (node (ref "T7") (pin "1") (pinfunction "B_1") (pintype "passive"))
    )
    (net (code "78") (name "SCL1") (class "Default")
      (node (ref "IC1") (pin "29") (pinfunction "PE1_29") (pintype "bidirectional"))
      (node (ref "X1") (pin "B6") (pinfunction "B6_B6") (pintype "bidirectional"))
    )
    (net (code "79") (name "SCL2") (class "Default")
      (node (ref "IC1") (pin "11") (pinfunction "PC1_11") (pintype "bidirectional"))
      (node (ref "X1") (pin "A9") (pinfunction "A9_A9") (pintype "bidirectional"))
    )
    (net (code "80") (name "SDA1") (class "Default")
      (node (ref "IC1") (pin "28") (pinfunction "PE0_28") (pintype "bidirectional"))
      (node (ref "X1") (pin "B8") (pinfunction "B8_B8") (pintype "bidirectional"))
    )
    (net (code "81") (name "SDA2") (class "Default")
      (node (ref "IC1") (pin "10") (pinfunction "PC0_10") (pintype "bidirectional"))
      (node (ref "X1") (pin "A11") (pinfunction "A11_A11") (pintype "bidirectional"))
    )
    (net (code "82") (name "TRIAC_OUT") (class "Default")
      (node (ref "IC1") (pin "17") (pinfunction "PC7_17") (pintype "bidirectional"))
      (node (ref "R4") (pin "2") (pinfunction "2_2") (pintype "passive"))
    )
    (net (code "83") (name "ZEROCROSS_IN") (class "Default")
      (node (ref "IC1") (pin "27") (pinfunction "PD7_27") (pintype "bidirectional"))
      (node (ref "OK2") (pin "10") (pinfunction "C_10") (pintype "passive"))
      (node (ref "R21") (pin "1") (pinfunction "1_1") (pintype "passive"))
    )
    (net (code "84") (name "unconnected-(JTAG-Pad3)") (class "Default")
      (node (ref "JTAG") (pin "3") (pinfunction "3_3") (pintype "passive"))
    )
    (net (code "85") (name "unconnected-(JTAG-Pad4)") (class "Default")
      (node (ref "JTAG") (pin "4") (pinfunction "4_4") (pintype "passive"))
    )
  )
)
